# WR_Mezzanine.net
KiCad netlist of a schematic drawn in Altium Designer
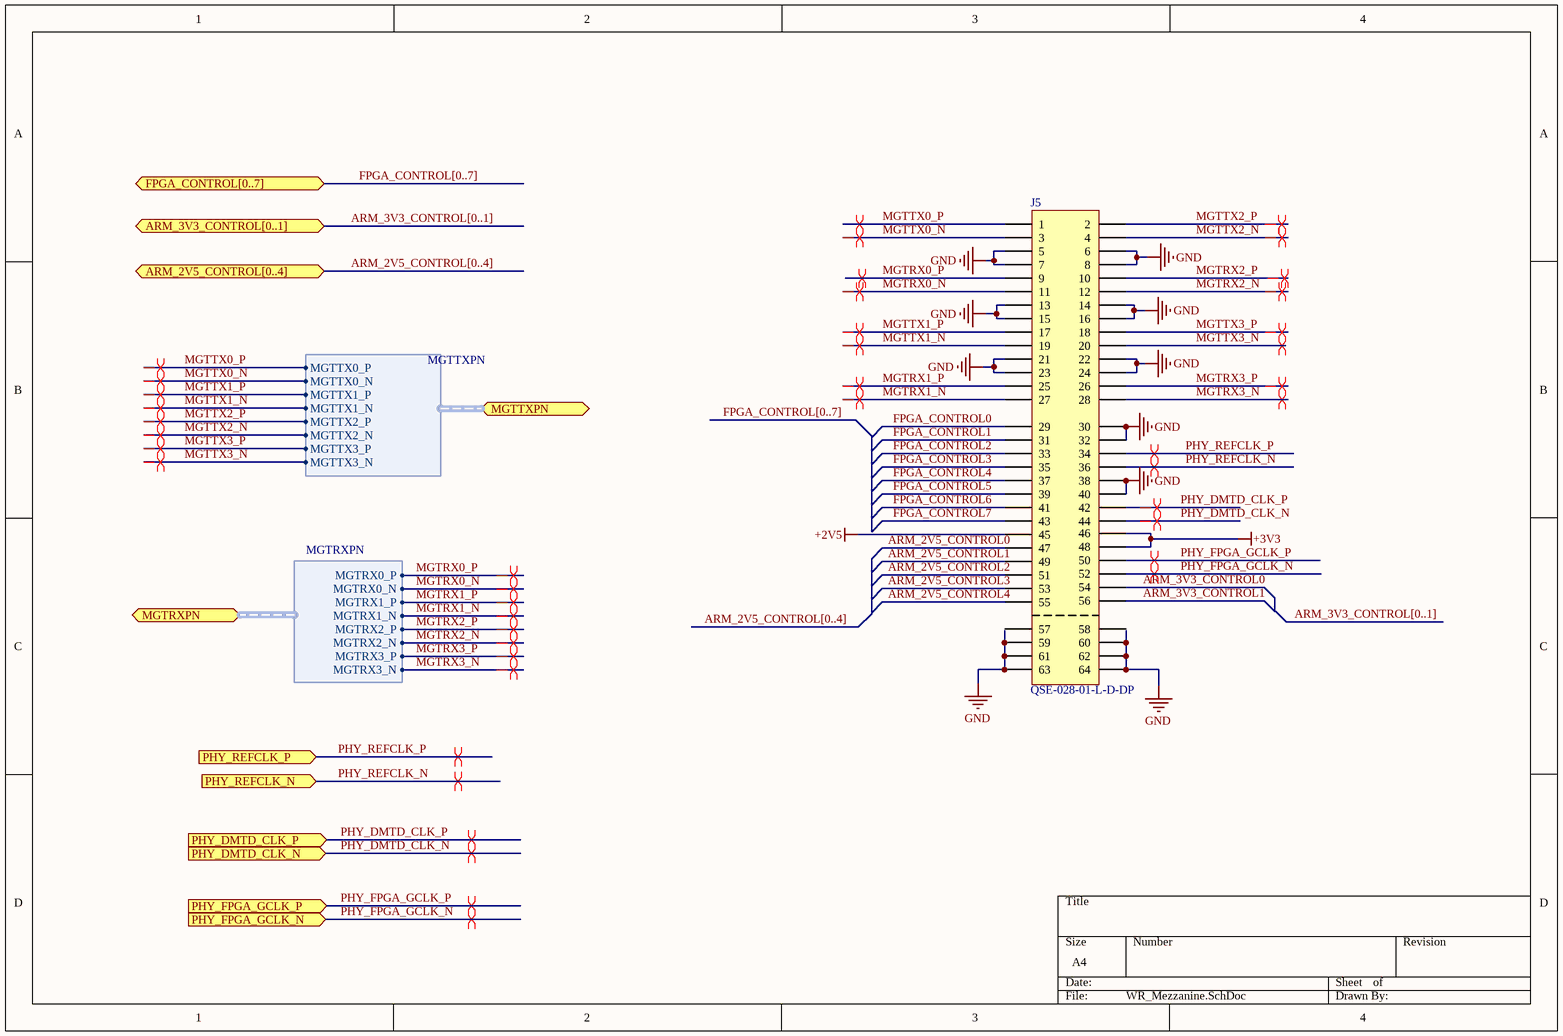
[diagram p0: WR_Mezzanine.SchDoc]

(export (version "E")
  (design (tool "Eeschema 10.0.6"))
  (components
    (comp (ref "J5")
      (value "QSE-028-01-L-D-DP")
      (footprint "7S_WR:QSE-028-01-X-D-DP-A")
      (description "High Speed Ground Plane Header")
      (libsource (lib "wr_switch") (part "QSE-028-01-L-D-DP"))
    )
  )
  (nets
    (net (code "3") (name "+2V5") (class "Default")
      (node (ref "J5") (pin "45") (pinfunction "45_45") (pintype "passive"))
    )
    (net (code "4") (name "+3V3") (class "Default")
      (node (ref "J5") (pin "46") (pinfunction "46_46") (pintype "passive"))
      (node (ref "J5") (pin "48") (pinfunction "48_48") (pintype "passive"))
    )
    (net (code "5") (name "/ARM_2V5_CONTROL0") (class "Default")
      (node (ref "J5") (pin "47") (pinfunction "47_47") (pintype "passive"))
    )
    (net (code "6") (name "/ARM_2V5_CONTROL1") (class "Default")
      (node (ref "J5") (pin "49") (pinfunction "49_49") (pintype "passive"))
    )
    (net (code "7") (name "/ARM_2V5_CONTROL2") (class "Default")
      (node (ref "J5") (pin "51") (pinfunction "51_51") (pintype "passive"))
    )
    (net (code "8") (name "/ARM_2V5_CONTROL3") (class "Default")
      (node (ref "J5") (pin "53") (pinfunction "53_53") (pintype "passive"))
    )
    (net (code "9") (name "/ARM_2V5_CONTROL4") (class "Default")
      (node (ref "J5") (pin "55") (pinfunction "55_55") (pintype "passive"))
    )
    (net (code "11") (name "/ARM_3V3_CONTROL0") (class "Default")
      (node (ref "J5") (pin "54") (pinfunction "54_54") (pintype "passive"))
    )
    (net (code "12") (name "/ARM_3V3_CONTROL1") (class "Default")
      (node (ref "J5") (pin "56") (pinfunction "56_56") (pintype "passive"))
    )
    (net (code "14") (name "/FPGA_CONTROL0") (class "Default")
      (node (ref "J5") (pin "29") (pinfunction "29_29") (pintype "passive"))
    )
    (net (code "15") (name "/FPGA_CONTROL1") (class "Default")
      (node (ref "J5") (pin "31") (pinfunction "31_31") (pintype "passive"))
    )
    (net (code "16") (name "/FPGA_CONTROL2") (class "Default")
      (node (ref "J5") (pin "33") (pinfunction "33_33") (pintype "passive"))
    )
    (net (code "17") (name "/FPGA_CONTROL3") (class "Default")
      (node (ref "J5") (pin "35") (pinfunction "35_35") (pintype "passive"))
    )
    (net (code "18") (name "/FPGA_CONTROL4") (class "Default")
      (node (ref "J5") (pin "37") (pinfunction "37_37") (pintype "passive"))
    )
    (net (code "19") (name "/FPGA_CONTROL5") (class "Default")
      (node (ref "J5") (pin "39") (pinfunction "39_39") (pintype "passive"))
    )
    (net (code "20") (name "/FPGA_CONTROL6") (class "Default")
      (node (ref "J5") (pin "41") (pinfunction "41_41") (pintype "passive"))
    )
    (net (code "21") (name "/FPGA_CONTROL7") (class "Default")
      (node (ref "J5") (pin "43") (pinfunction "43_43") (pintype "passive"))
    )
    (net (code "23") (name "/MGTRX0_N") (class "Default")
      (node (ref "J5") (pin "11") (pinfunction "11_11") (pintype "passive"))
    )
    (net (code "24") (name "/MGTRX0_P") (class "Default")
      (node (ref "J5") (pin "9") (pinfunction "9_9") (pintype "passive"))
    )
    (net (code "25") (name "/MGTRX1_N") (class "Default")
      (node (ref "J5") (pin "27") (pinfunction "27_27") (pintype "passive"))
    )
    (net (code "26") (name "/MGTRX1_P") (class "Default")
      (node (ref "J5") (pin "25") (pinfunction "25_25") (pintype "passive"))
    )
    (net (code "27") (name "/MGTRX2_N") (class "Default")
      (node (ref "J5") (pin "12") (pinfunction "12_12") (pintype "passive"))
    )
    (net (code "28") (name "/MGTRX2_P") (class "Default")
      (node (ref "J5") (pin "10") (pinfunction "10_10") (pintype "passive"))
    )
    (net (code "29") (name "/MGTRX3_N") (class "Default")
      (node (ref "J5") (pin "28") (pinfunction "28_28") (pintype "passive"))
    )
    (net (code "30") (name "/MGTRX3_P") (class "Default")
      (node (ref "J5") (pin "26") (pinfunction "26_26") (pintype "passive"))
    )
    (net (code "31") (name "/MGTTX0_N") (class "Default")
      (node (ref "J5") (pin "3") (pinfunction "3_3") (pintype "passive"))
    )
    (net (code "32") (name "/MGTTX0_P") (class "Default")
      (node (ref "J5") (pin "1") (pinfunction "1_1") (pintype "passive"))
    )
    (net (code "33") (name "/MGTTX1_N") (class "Default")
      (node (ref "J5") (pin "19") (pinfunction "19_19") (pintype "passive"))
    )
    (net (code "34") (name "/MGTTX1_P") (class "Default")
      (node (ref "J5") (pin "17") (pinfunction "17_17") (pintype "passive"))
    )
    (net (code "35") (name "/MGTTX2_N") (class "Default")
      (node (ref "J5") (pin "4") (pinfunction "4_4") (pintype "passive"))
    )
    (net (code "36") (name "/MGTTX2_P") (class "Default")
      (node (ref "J5") (pin "2") (pinfunction "2_2") (pintype "passive"))
    )
    (net (code "37") (name "/MGTTX3_N") (class "Default")
      (node (ref "J5") (pin "20") (pinfunction "20_20") (pintype "passive"))
    )
    (net (code "38") (name "/MGTTX3_P") (class "Default")
      (node (ref "J5") (pin "18") (pinfunction "18_18") (pintype "passive"))
    )
    (net (code "39") (name "/PHY_DMTD_CLK_N") (class "Default")
      (node (ref "J5") (pin "44") (pinfunction "44_44") (pintype "passive"))
    )
    (net (code "40") (name "/PHY_DMTD_CLK_P") (class "Default")
      (node (ref "J5") (pin "42") (pinfunction "42_42") (pintype "passive"))
    )
    (net (code "41") (name "/PHY_FPGA_GCLK_N") (class "Default")
      (node (ref "J5") (pin "52") (pinfunction "52_52") (pintype "passive"))
    )
    (net (code "42") (name "/PHY_FPGA_GCLK_P") (class "Default")
      (node (ref "J5") (pin "50") (pinfunction "50_50") (pintype "passive"))
    )
    (net (code "43") (name "/PHY_REFCLK_N") (class "Default")
      (node (ref "J5") (pin "36") (pinfunction "36_36") (pintype "passive"))
    )
    (net (code "44") (name "/PHY_REFCLK_P") (class "Default")
      (node (ref "J5") (pin "34") (pinfunction "34_34") (pintype "passive"))
    )
    (net (code "47") (name "GND") (class "Default")
      (node (ref "J5") (pin "13") (pinfunction "13_13") (pintype "passive"))
      (node (ref "J5") (pin "14") (pinfunction "14_14") (pintype "passive"))
      (node (ref "J5") (pin "15") (pinfunction "15_15") (pintype "passive"))
      (node (ref "J5") (pin "16") (pinfunction "16_16") (pintype "passive"))
      (node (ref "J5") (pin "21") (pinfunction "21_21") (pintype "passive"))
      (node (ref "J5") (pin "22") (pinfunction "22_22") (pintype "passive"))
      (node (ref "J5") (pin "23") (pinfunction "23_23") (pintype "passive"))
      (node (ref "J5") (pin "24") (pinfunction "24_24") (pintype "passive"))
      (node (ref "J5") (pin "30") (pinfunction "30_30") (pintype "passive"))
      (node (ref "J5") (pin "32") (pinfunction "32_32") (pintype "passive"))
      (node (ref "J5") (pin "38") (pinfunction "38_38") (pintype "passive"))
      (node (ref "J5") (pin "40") (pinfunction "40_40") (pintype "passive"))
      (node (ref "J5") (pin "5") (pinfunction "5_5") (pintype "passive"))
      (node (ref "J5") (pin "59") (pinfunction "59_59") (pintype "passive"))
      (node (ref "J5") (pin "6") (pinfunction "6_6") (pintype "passive"))
      (node (ref "J5") (pin "60") (pinfunction "60_60") (pintype "passive"))
      (node (ref "J5") (pin "61") (pinfunction "61_61") (pintype "passive"))
      (node (ref "J5") (pin "62") (pinfunction "62_62") (pintype "passive"))
      (node (ref "J5") (pin "63") (pinfunction "63_63") (pintype "passive"))
      (node (ref "J5") (pin "64") (pinfunction "64_64") (pintype "passive"))
      (node (ref "J5") (pin "7") (pinfunction "7_7") (pintype "passive"))
      (node (ref "J5") (pin "8") (pinfunction "8_8") (pintype "passive"))
    )
    (net (code "48") (name "unconnected-(J5-Pad57)") (class "Default")
      (node (ref "J5") (pin "57") (pinfunction "57_57") (pintype "passive"))
    )
    (net (code "49") (name "unconnected-(J5-Pad58)") (class "Default")
      (node (ref "J5") (pin "58") (pinfunction "58_58") (pintype "passive"))
    )
  )
)
